# batsim1_2.net
KiCad netlist of a schematic drawn in EAGLE
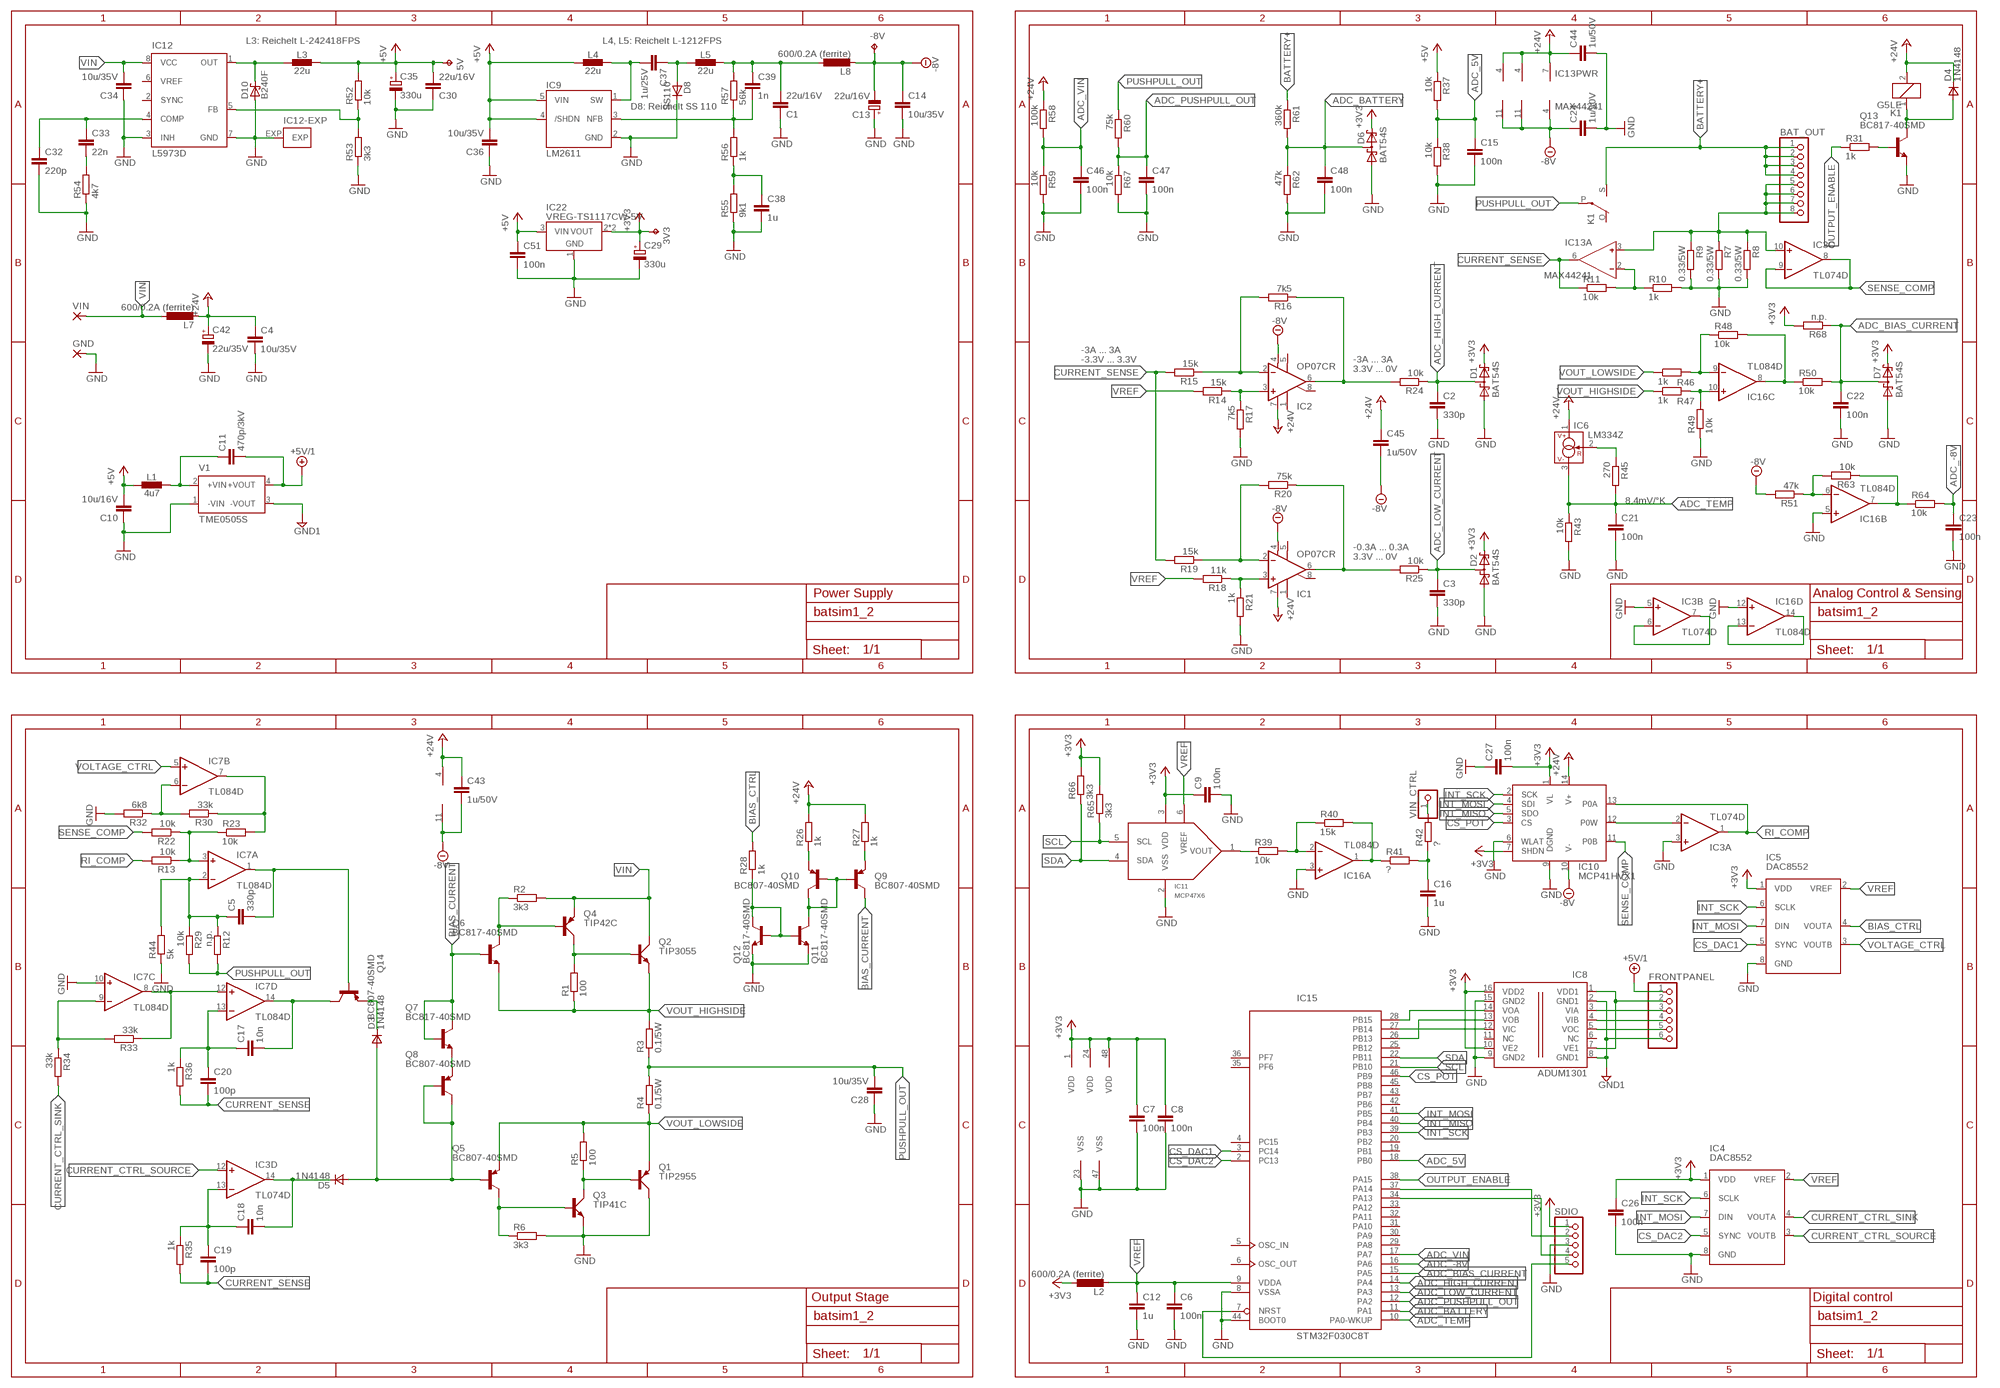
[diagram p0: schematic, sheet 1]

(export (version "E")
  (design (tool "Eeschema 10.0.6"))
  (components
    (comp (ref "-8V")
      (value "TPB1,27")
      (footprint "eagle-import:B1,27")
      (libsource (lib "eagle-import") (part "TPB1,27"))
    )
    (comp (ref "3V3")
      (value "TPB1,27")
      (footprint "eagle-import:B1,27")
      (libsource (lib "eagle-import") (part "TPB1,27"))
    )
    (comp (ref "5V")
      (value "TPB1,27")
      (footprint "eagle-import:B1,27")
      (libsource (lib "eagle-import") (part "TPB1,27"))
    )
    (comp (ref "BAT_OUT")
      (value "PINHD-1X8/90")
      (footprint "eagle-import:1X08_90")
      (libsource (lib "eagle-import") (part "PINHD-1X8/90"))
    )
    (comp (ref "C1")
      (value "22u/16V")
      (footprint "eagle-import:C1206")
      (libsource (lib "eagle-import") (part "C-EUC1206"))
    )
    (comp (ref "C2")
      (value "330p")
      (footprint "eagle-import:C0603")
      (libsource (lib "eagle-import") (part "C-EUC0603"))
    )
    (comp (ref "C3")
      (value "330p")
      (footprint "eagle-import:C0603")
      (libsource (lib "eagle-import") (part "C-EUC0603"))
    )
    (comp (ref "C4")
      (value "10u/35V")
      (footprint "eagle-import:C1206")
      (libsource (lib "eagle-import") (part "C-EUC1206"))
    )
    (comp (ref "C5")
      (value "330p")
      (footprint "eagle-import:C0603")
      (libsource (lib "eagle-import") (part "C-EUC0603"))
    )
    (comp (ref "C6")
      (value "100n")
      (footprint "eagle-import:C0603")
      (libsource (lib "eagle-import") (part "C-EUC0603"))
    )
    (comp (ref "C7")
      (value "100n")
      (footprint "eagle-import:C0603")
      (libsource (lib "eagle-import") (part "C-EUC0603"))
    )
    (comp (ref "C8")
      (value "100n")
      (footprint "eagle-import:C0603")
      (libsource (lib "eagle-import") (part "C-EUC0603"))
    )
    (comp (ref "C9")
      (value "100n")
      (footprint "eagle-import:C0603")
      (libsource (lib "eagle-import") (part "C-EUC0603"))
    )
    (comp (ref "C10")
      (value "10u/16V")
      (footprint "eagle-import:C1206")
      (libsource (lib "eagle-import") (part "C-EUC1206"))
    )
    (comp (ref "C11")
      (value "470p/3kV")
      (footprint "eagle-import:C1812")
      (libsource (lib "eagle-import") (part "resistor_C-EUC1812"))
    )
    (comp (ref "C12")
      (value "1u")
      (footprint "eagle-import:C0603")
      (libsource (lib "eagle-import") (part "C-EUC0603"))
    )
    (comp (ref "C13")
      (value "22u/16V")
      (footprint "eagle-import:153CLV-0505")
      (libsource (lib "eagle-import") (part "CPOL-EU153CLV-0505"))
    )
    (comp (ref "C14")
      (value "10u/35V")
      (footprint "eagle-import:C1206")
      (libsource (lib "eagle-import") (part "C-EUC1206"))
    )
    (comp (ref "C15")
      (value "100n")
      (footprint "eagle-import:C0603")
      (libsource (lib "eagle-import") (part "C-EUC0603"))
    )
    (comp (ref "C16")
      (value "1u")
      (footprint "eagle-import:C0603")
      (libsource (lib "eagle-import") (part "C-EUC0603"))
    )
    (comp (ref "C17")
      (value "10n")
      (footprint "eagle-import:C0603")
      (libsource (lib "eagle-import") (part "C-EUC0603"))
    )
    (comp (ref "C18")
      (value "10n")
      (footprint "eagle-import:C0603")
      (libsource (lib "eagle-import") (part "C-EUC0603"))
    )
    (comp (ref "C19")
      (value "100p")
      (footprint "eagle-import:C0603")
      (libsource (lib "eagle-import") (part "C-EUC0603"))
    )
    (comp (ref "C20")
      (value "100p")
      (footprint "eagle-import:C0603")
      (libsource (lib "eagle-import") (part "C-EUC0603"))
    )
    (comp (ref "C21")
      (value "100n")
      (footprint "eagle-import:C0603")
      (libsource (lib "eagle-import") (part "C-EUC0603"))
    )
    (comp (ref "C22")
      (value "100n")
      (footprint "eagle-import:C0603")
      (libsource (lib "eagle-import") (part "C-EUC0603"))
    )
    (comp (ref "C23")
      (value "100n")
      (footprint "eagle-import:C0603")
      (libsource (lib "eagle-import") (part "C-EUC0603"))
    )
    (comp (ref "C24")
      (value "1u/50V")
      (footprint "eagle-import:C0603")
      (libsource (lib "eagle-import") (part "C-EUC0603"))
    )
    (comp (ref "C26")
      (value "100n")
      (footprint "eagle-import:C0603")
      (libsource (lib "eagle-import") (part "C-EUC0603"))
    )
    (comp (ref "C27")
      (value "100n")
      (footprint "eagle-import:C0603")
      (libsource (lib "eagle-import") (part "C-EUC0603"))
    )
    (comp (ref "C28")
      (value "10u/35V")
      (footprint "eagle-import:C1206")
      (libsource (lib "eagle-import") (part "C-EUC1206"))
    )
    (comp (ref "C29")
      (value "330u")
      (footprint "eagle-import:153CLV-0605")
      (libsource (lib "eagle-import") (part "CPOL-EU153CLV-0605"))
    )
    (comp (ref "C30")
      (value "22u/16V")
      (footprint "eagle-import:C1206")
      (libsource (lib "eagle-import") (part "C-EUC1206"))
    )
    (comp (ref "C32")
      (value "220p")
      (footprint "eagle-import:C0603")
      (libsource (lib "eagle-import") (part "C-EUC0603"))
    )
    (comp (ref "C33")
      (value "22n")
      (footprint "eagle-import:C0603")
      (libsource (lib "eagle-import") (part "C-EUC0603"))
    )
    (comp (ref "C34")
      (value "10u/35V")
      (footprint "eagle-import:C1206")
      (libsource (lib "eagle-import") (part "C-EUC1206"))
    )
    (comp (ref "C35")
      (value "330u")
      (footprint "eagle-import:153CLV-0605")
      (libsource (lib "eagle-import") (part "CPOL-EU153CLV-0605"))
    )
    (comp (ref "C36")
      (value "10u/35V")
      (footprint "eagle-import:C1206")
      (libsource (lib "eagle-import") (part "C-EUC1206"))
    )
    (comp (ref "C37")
      (value "1u/25V")
      (footprint "eagle-import:C1206")
      (libsource (lib "eagle-import") (part "C-EUC1206"))
    )
    (comp (ref "C38")
      (value "1u")
      (footprint "eagle-import:C0603")
      (libsource (lib "eagle-import") (part "C-EUC0603"))
    )
    (comp (ref "C39")
      (value "1n")
      (footprint "eagle-import:C0603")
      (libsource (lib "eagle-import") (part "C-EUC0603"))
    )
    (comp (ref "C42")
      (value "22u/35V")
      (footprint "eagle-import:153CLV-0605")
      (libsource (lib "eagle-import") (part "CPOL-EU153CLV-0605"))
    )
    (comp (ref "C43")
      (value "1u/50V")
      (footprint "eagle-import:C0603")
      (libsource (lib "eagle-import") (part "C-EUC0603"))
    )
    (comp (ref "C44")
      (value "1u/50V")
      (footprint "eagle-import:C0603")
      (libsource (lib "eagle-import") (part "C-EUC0603"))
    )
    (comp (ref "C45")
      (value "1u/50V")
      (footprint "eagle-import:C0603")
      (libsource (lib "eagle-import") (part "C-EUC0603"))
    )
    (comp (ref "C46")
      (value "100n")
      (footprint "eagle-import:C0603")
      (libsource (lib "eagle-import") (part "C-EUC0603"))
    )
    (comp (ref "C47")
      (value "100n")
      (footprint "eagle-import:C0603")
      (libsource (lib "eagle-import") (part "C-EUC0603"))
    )
    (comp (ref "C48")
      (value "100n")
      (footprint "eagle-import:C0603")
      (libsource (lib "eagle-import") (part "C-EUC0603"))
    )
    (comp (ref "C51")
      (value "100n")
      (footprint "eagle-import:C0603")
      (libsource (lib "eagle-import") (part "C-EUC0603"))
    )
    (comp (ref "D1")
      (value "BAT54S")
      (footprint "eagle-import:SOT23")
      (libsource (lib "eagle-import") (part "BAT54S"))
    )
    (comp (ref "D2")
      (value "BAT54S")
      (footprint "eagle-import:SOT23")
      (libsource (lib "eagle-import") (part "BAT54S"))
    )
    (comp (ref "D3")
      (value "1N4148")
      (footprint "eagle-import:SOD323")
      (fields (field (name "MPN") "CDSOD323-T05C"))
      (libsource (lib "eagle-import") (part "DSOD323"))
    )
    (comp (ref "D4")
      (value "1N4148")
      (footprint "eagle-import:SOD323")
      (fields (field (name "MPN") "CDSOD323-T05C"))
      (libsource (lib "eagle-import") (part "DSOD323"))
    )
    (comp (ref "D5")
      (value "1N4148")
      (footprint "eagle-import:SOD323")
      (fields (field (name "MPN") "CDSOD323-T05C"))
      (libsource (lib "eagle-import") (part "DSOD323"))
    )
    (comp (ref "D6")
      (value "BAT54S")
      (footprint "eagle-import:SOT23")
      (libsource (lib "eagle-import") (part "BAT54S"))
    )
    (comp (ref "D7")
      (value "BAT54S")
      (footprint "eagle-import:SOT23")
      (libsource (lib "eagle-import") (part "BAT54S"))
    )
    (comp (ref "D8")
      (value "SS110")
      (footprint "eagle-import:SMA")
      (libsource (lib "eagle-import") (part "D-SMA"))
    )
    (comp (ref "D10")
      (value "B240F")
      (footprint "eagle-import:SMB")
      (libsource (lib "eagle-import") (part "SCHOTTKY-DIODESMD"))
    )
    (comp (ref "FRONTPANEL")
      (value "PINHD-1X6/90")
      (footprint "eagle-import:1X06_90")
      (libsource (lib "eagle-import") (part "PINHD-1X6/90"))
    )
    (comp (ref "GND")
      (value "3,81/1,4")
      (footprint "eagle-import:3,81_1,4")
      (libsource (lib "eagle-import") (part "3,81/1,4"))
    )
    (comp (ref "IC1")
      (value "OP07CR")
      (footprint "eagle-import:SO08")
      (libsource (lib "eagle-import") (part "OP07RC"))
    )
    (comp (ref "IC2")
      (value "OP07CR")
      (footprint "eagle-import:SO08")
      (libsource (lib "eagle-import") (part "OP07RC"))
    )
    (comp (ref "IC3")
      (value "TL074D")
      (footprint "eagle-import:SO14")
      (libsource (lib "eagle-import") (part "TL074D"))
    )
    (comp (ref "IC4")
      (value "DAC8552")
      (footprint "eagle-import:MSOP8")
      (libsource (lib "eagle-import") (part "DAC8552"))
    )
    (comp (ref "IC5")
      (value "DAC8552")
      (footprint "eagle-import:MSOP8")
      (libsource (lib "eagle-import") (part "DAC8552"))
    )
    (comp (ref "IC6")
      (value "LM334Z")
      (footprint "eagle-import:TO92")
      (libsource (lib "eagle-import") (part "LM34Z3"))
    )
    (comp (ref "IC7")
      (value "TL084D")
      (footprint "eagle-import:SO14")
      (libsource (lib "eagle-import") (part "TL084D"))
    )
    (comp (ref "IC8")
      (value "ADUM1301")
      (footprint "eagle-import:SO-16W")
      (fields (field (name "MPN") "ADUM1301BRWZ"))
      (libsource (lib "eagle-import") (part "ADUM1301"))
    )
    (comp (ref "IC9")
      (value "LM2611")
      (footprint "eagle-import:SOT23-5")
      (libsource (lib "eagle-import") (part "LM2611"))
    )
    (comp (ref "IC10")
      (value "MCP41HVX1")
      (footprint "eagle-import:TSSOP14")
      (libsource (lib "eagle-import") (part "MCP41HVX1"))
    )
    (comp (ref "IC11")
      (value "MCP47X6")
      (footprint "eagle-import:SOT23-6L")
      (libsource (lib "eagle-import") (part "MCP47X6"))
    )
    (comp (ref "IC12")
      (value "L5973D")
      (footprint "eagle-import:HSOP8")
      (fields (field (name "MF") "STMICROELECTRONICS"))
      (libsource (lib "eagle-import") (part "L5973D"))
    )
    (comp (ref "IC13")
      (value "MAX44241")
      (footprint "eagle-import:UMAX8")
      (libsource (lib "eagle-import") (part "MAX44241"))
    )
    (comp (ref "IC15")
      (value "STM32F030C8T")
      (footprint "eagle-import:LQFP48")
      (libsource (lib "eagle-import") (part "STM32F030CT8"))
    )
    (comp (ref "IC16")
      (value "TL084D")
      (footprint "eagle-import:SO14")
      (libsource (lib "eagle-import") (part "TL084D"))
    )
    (comp (ref "IC22")
      (value "VREG-TS1117CW-5V")
      (footprint "eagle-import:SOT223")
      (libsource (lib "eagle-import") (part "VREG-TS1117CW-5V"))
    )
    (comp (ref "K1")
      (value "G5LE")
      (footprint "eagle-import:G5LE")
      (libsource (lib "eagle-import") (part "G5LE"))
    )
    (comp (ref "L1")
      (value "4u7")
      (footprint "eagle-import:L_1212")
      (libsource (lib "eagle-import") (part "INDUCTOR-1212"))
    )
    (comp (ref "L2")
      (value "600/0.2A (ferrite)")
      (footprint "eagle-import:L2012C")
      (libsource (lib "eagle-import") (part "L-EUL2012C"))
    )
    (comp (ref "L3")
      (value "22u")
      (footprint "eagle-import:L_NR60XX")
      (libsource (lib "eagle-import") (part "INDUCTOR-NR60XX"))
    )
    (comp (ref "L4")
      (value "22u")
      (footprint "eagle-import:L_1212")
      (libsource (lib "eagle-import") (part "INDUCTOR-1212"))
    )
    (comp (ref "L5")
      (value "22u")
      (footprint "eagle-import:L_1212")
      (libsource (lib "eagle-import") (part "INDUCTOR-1212"))
    )
    (comp (ref "L7")
      (value "600/0.2A (ferrite)")
      (footprint "eagle-import:L2012C")
      (libsource (lib "eagle-import") (part "L-EUL2012C"))
    )
    (comp (ref "L8")
      (value "600/0.2A (ferrite)")
      (footprint "eagle-import:L2012C")
      (libsource (lib "eagle-import") (part "L-EUL2012C"))
    )
    (comp (ref "Q1")
      (value "TIP2955")
      (footprint "eagle-import:TOP3AV")
      (libsource (lib "eagle-import") (part "TIP2955"))
    )
    (comp (ref "Q2")
      (value "TIP3055")
      (footprint "eagle-import:TOP3AV")
      (libsource (lib "eagle-import") (part "TIP3055"))
    )
    (comp (ref "Q3")
      (value "TIP41C")
      (footprint "eagle-import:TO220AV")
      (libsource (lib "eagle-import") (part "TIP41C"))
    )
    (comp (ref "Q4")
      (value "TIP42C")
      (footprint "eagle-import:TO220AV")
      (libsource (lib "eagle-import") (part "TIP42C"))
    )
    (comp (ref "Q5")
      (value "BC807-40SMD")
      (footprint "eagle-import:SOT23-BEC")
      (libsource (lib "eagle-import") (part "BC807SMD-40"))
    )
    (comp (ref "Q6")
      (value "BC817-40SMD")
      (footprint "eagle-import:SOT23-BEC")
      (libsource (lib "eagle-import") (part "BC817SMD-40"))
    )
    (comp (ref "Q7")
      (value "BC817-40SMD")
      (footprint "eagle-import:SOT23-BEC")
      (libsource (lib "eagle-import") (part "BC817SMD-40"))
    )
    (comp (ref "Q8")
      (value "BC807-40SMD")
      (footprint "eagle-import:SOT23-BEC")
      (libsource (lib "eagle-import") (part "BC807SMD-40"))
    )
    (comp (ref "Q9")
      (value "BC807-40SMD")
      (footprint "eagle-import:SOT23-BEC")
      (libsource (lib "eagle-import") (part "BC807SMD-40"))
    )
    (comp (ref "Q10")
      (value "BC807-40SMD")
      (footprint "eagle-import:SOT23-BEC")
      (libsource (lib "eagle-import") (part "BC807SMD-40"))
    )
    (comp (ref "Q11")
      (value "BC817-40SMD")
      (footprint "eagle-import:SOT23-BEC")
      (libsource (lib "eagle-import") (part "BC817SMD-40"))
    )
    (comp (ref "Q12")
      (value "BC817-40SMD")
      (footprint "eagle-import:SOT23-BEC")
      (libsource (lib "eagle-import") (part "BC817SMD-40"))
    )
    (comp (ref "Q13")
      (value "BC817-40SMD")
      (footprint "eagle-import:SOT23-BEC")
      (libsource (lib "eagle-import") (part "BC817SMD-40"))
    )
    (comp (ref "Q14")
      (value "BC807-40SMD")
      (footprint "eagle-import:SOT23-BEC")
      (libsource (lib "eagle-import") (part "BC807SMD-40"))
    )
    (comp (ref "R1")
      (value "100")
      (footprint "eagle-import:R0603")
      (libsource (lib "eagle-import") (part "R-EU_R0603"))
    )
    (comp (ref "R2")
      (value "3k3")
      (footprint "eagle-import:R0603")
      (libsource (lib "eagle-import") (part "R-EU_R0603"))
    )
    (comp (ref "R3")
      (value "0.1/5W")
      (footprint "eagle-import:5WAXIAL")
      (libsource (lib "eagle-import") (part "5WAXIAL"))
    )
    (comp (ref "R4")
      (value "0.1/5W")
      (footprint "eagle-import:5WAXIAL")
      (libsource (lib "eagle-import") (part "5WAXIAL"))
    )
    (comp (ref "R5")
      (value "100")
      (footprint "eagle-import:R0603")
      (libsource (lib "eagle-import") (part "R-EU_R0603"))
    )
    (comp (ref "R6")
      (value "3k3")
      (footprint "eagle-import:R0603")
      (libsource (lib "eagle-import") (part "R-EU_R0603"))
    )
    (comp (ref "R7")
      (value "0.33/5W")
      (footprint "eagle-import:5WAXIAL")
      (libsource (lib "eagle-import") (part "5WAXIAL"))
    )
    (comp (ref "R8")
      (value "0.33/5W")
      (footprint "eagle-import:5WAXIAL")
      (libsource (lib "eagle-import") (part "5WAXIAL"))
    )
    (comp (ref "R9")
      (value "0.33/5W")
      (footprint "eagle-import:5WAXIAL")
      (libsource (lib "eagle-import") (part "5WAXIAL"))
    )
    (comp (ref "R10")
      (value "1k")
      (footprint "eagle-import:R0603")
      (libsource (lib "eagle-import") (part "R-EU_R0603"))
    )
    (comp (ref "R11")
      (value "10k")
      (footprint "eagle-import:R0603")
      (libsource (lib "eagle-import") (part "R-EU_R0603"))
    )
    (comp (ref "R12")
      (value "n.p.")
      (footprint "eagle-import:R0603")
      (libsource (lib "eagle-import") (part "R-EU_R0603"))
    )
    (comp (ref "R13")
      (value "10k")
      (footprint "eagle-import:R0603")
      (libsource (lib "eagle-import") (part "R-EU_R0603"))
    )
    (comp (ref "R14")
      (value "15k")
      (footprint "eagle-import:R0603")
      (libsource (lib "eagle-import") (part "R-EU_R0603"))
    )
    (comp (ref "R15")
      (value "15k")
      (footprint "eagle-import:R0603")
      (libsource (lib "eagle-import") (part "R-EU_R0603"))
    )
    (comp (ref "R16")
      (value "7k5")
      (footprint "eagle-import:R0603")
      (libsource (lib "eagle-import") (part "R-EU_R0603"))
    )
    (comp (ref "R17")
      (value "7k5")
      (footprint "eagle-import:R0603")
      (libsource (lib "eagle-import") (part "R-EU_R0603"))
    )
    (comp (ref "R18")
      (value "11k")
      (footprint "eagle-import:R0603")
      (libsource (lib "eagle-import") (part "R-EU_R0603"))
    )
    (comp (ref "R19")
      (value "15k")
      (footprint "eagle-import:R0603")
      (libsource (lib "eagle-import") (part "R-EU_R0603"))
    )
    (comp (ref "R20")
      (value "75k")
      (footprint "eagle-import:R0603")
      (libsource (lib "eagle-import") (part "R-EU_R0603"))
    )
    (comp (ref "R21")
      (value "1k")
      (footprint "eagle-import:R0603")
      (libsource (lib "eagle-import") (part "R-EU_R0603"))
    )
    (comp (ref "R22")
      (value "10k")
      (footprint "eagle-import:R0603")
      (libsource (lib "eagle-import") (part "R-EU_R0603"))
    )
    (comp (ref "R23")
      (value "10k")
      (footprint "eagle-import:R0603")
      (libsource (lib "eagle-import") (part "R-EU_R0603"))
    )
    (comp (ref "R24")
      (value "10k")
      (footprint "eagle-import:R0603")
      (libsource (lib "eagle-import") (part "R-EU_R0603"))
    )
    (comp (ref "R25")
      (value "10k")
      (footprint "eagle-import:R0603")
      (libsource (lib "eagle-import") (part "R-EU_R0603"))
    )
    (comp (ref "R26")
      (value "1k")
      (footprint "eagle-import:R0603")
      (libsource (lib "eagle-import") (part "R-EU_R0603"))
    )
    (comp (ref "R27")
      (value "1k")
      (footprint "eagle-import:R0603")
      (libsource (lib "eagle-import") (part "R-EU_R0603"))
    )
    (comp (ref "R28")
      (value "1k")
      (footprint "eagle-import:R0603")
      (libsource (lib "eagle-import") (part "R-EU_R0603"))
    )
    (comp (ref "R29")
      (value "10k")
      (footprint "eagle-import:R0603")
      (libsource (lib "eagle-import") (part "R-EU_R0603"))
    )
    (comp (ref "R30")
      (value "33k")
      (footprint "eagle-import:R0603")
      (libsource (lib "eagle-import") (part "R-EU_R0603"))
    )
    (comp (ref "R31")
      (value "1k")
      (footprint "eagle-import:R0603")
      (libsource (lib "eagle-import") (part "R-EU_R0603"))
    )
    (comp (ref "R32")
      (value "6k8")
      (footprint "eagle-import:R0603")
      (libsource (lib "eagle-import") (part "R-EU_R0603"))
    )
    (comp (ref "R33")
      (value "33k")
      (footprint "eagle-import:R0603")
      (libsource (lib "eagle-import") (part "R-EU_R0603"))
    )
    (comp (ref "R34")
      (value "33k")
      (footprint "eagle-import:R0603")
      (libsource (lib "eagle-import") (part "R-EU_R0603"))
    )
    (comp (ref "R35")
      (value "1k")
      (footprint "eagle-import:R0603")
      (libsource (lib "eagle-import") (part "R-EU_R0603"))
    )
    (comp (ref "R36")
      (value "1k")
      (footprint "eagle-import:R0603")
      (libsource (lib "eagle-import") (part "R-EU_R0603"))
    )
    (comp (ref "R37")
      (value "10k")
      (footprint "eagle-import:R0603")
      (libsource (lib "eagle-import") (part "R-EU_R0603"))
    )
    (comp (ref "R38")
      (value "10k")
      (footprint "eagle-import:R0603")
      (libsource (lib "eagle-import") (part "R-EU_R0603"))
    )
    (comp (ref "R39")
      (value "10k")
      (footprint "eagle-import:R0603")
      (libsource (lib "eagle-import") (part "R-EU_R0603"))
    )
    (comp (ref "R40")
      (value "15k")
      (footprint "eagle-import:R0603")
      (libsource (lib "eagle-import") (part "R-EU_R0603"))
    )
    (comp (ref "R41")
      (value "?")
      (footprint "eagle-import:R0603")
      (libsource (lib "eagle-import") (part "R-EU_R0603"))
    )
    (comp (ref "R42")
      (value "?")
      (footprint "eagle-import:R0603")
      (libsource (lib "eagle-import") (part "R-EU_R0603"))
    )
    (comp (ref "R43")
      (value "10k")
      (footprint "eagle-import:R0603")
      (libsource (lib "eagle-import") (part "R-EU_R0603"))
    )
    (comp (ref "R44")
      (value "5k")
      (footprint "eagle-import:R0603")
      (libsource (lib "eagle-import") (part "R-EU_R0603"))
    )
    (comp (ref "R45")
      (value "270")
      (footprint "eagle-import:R0603")
      (libsource (lib "eagle-import") (part "R-EU_R0603"))
    )
    (comp (ref "R46")
      (value "1k")
      (footprint "eagle-import:R0603")
      (libsource (lib "eagle-import") (part "R-EU_R0603"))
    )
    (comp (ref "R47")
      (value "1k")
      (footprint "eagle-import:R0603")
      (libsource (lib "eagle-import") (part "R-EU_R0603"))
    )
    (comp (ref "R48")
      (value "10k")
      (footprint "eagle-import:R0603")
      (libsource (lib "eagle-import") (part "R-EU_R0603"))
    )
    (comp (ref "R49")
      (value "10k")
      (footprint "eagle-import:R0603")
      (libsource (lib "eagle-import") (part "R-EU_R0603"))
    )
    (comp (ref "R50")
      (value "10k")
      (footprint "eagle-import:R0603")
      (libsource (lib "eagle-import") (part "R-EU_R0603"))
    )
    (comp (ref "R51")
      (value "47k")
      (footprint "eagle-import:R0603")
      (libsource (lib "eagle-import") (part "R-EU_R0603"))
    )
    (comp (ref "R52")
      (value "10k")
      (footprint "eagle-import:R0603")
      (libsource (lib "eagle-import") (part "R-EU_R0603"))
    )
    (comp (ref "R53")
      (value "3k3")
      (footprint "eagle-import:R0603")
      (libsource (lib "eagle-import") (part "R-EU_R0603"))
    )
    (comp (ref "R54")
      (value "4k7")
      (footprint "eagle-import:R0603")
      (libsource (lib "eagle-import") (part "R-EU_R0603"))
    )
    (comp (ref "R55")
      (value "9k1")
      (footprint "eagle-import:R0603")
      (libsource (lib "eagle-import") (part "R-EU_R0603"))
    )
    (comp (ref "R56")
      (value "1k")
      (footprint "eagle-import:R0603")
      (libsource (lib "eagle-import") (part "R-EU_R0603"))
    )
    (comp (ref "R57")
      (value "56k")
      (footprint "eagle-import:R0603")
      (libsource (lib "eagle-import") (part "R-EU_R0603"))
    )
    (comp (ref "R58")
      (value "100k")
      (footprint "eagle-import:R0603")
      (libsource (lib "eagle-import") (part "R-EU_R0603"))
    )
    (comp (ref "R59")
      (value "10k")
      (footprint "eagle-import:R0603")
      (libsource (lib "eagle-import") (part "R-EU_R0603"))
    )
    (comp (ref "R60")
      (value "75k")
      (footprint "eagle-import:R0603")
      (libsource (lib "eagle-import") (part "R-EU_R0603"))
    )
    (comp (ref "R61")
      (value "360k")
      (footprint "eagle-import:R0603")
      (libsource (lib "eagle-import") (part "R-EU_R0603"))
    )
    (comp (ref "R62")
      (value "47k")
      (footprint "eagle-import:R0603")
      (libsource (lib "eagle-import") (part "R-EU_R0603"))
    )
    (comp (ref "R63")
      (value "10k")
      (footprint "eagle-import:R0603")
      (libsource (lib "eagle-import") (part "R-EU_R0603"))
    )
    (comp (ref "R64")
      (value "10k")
      (footprint "eagle-import:R0603")
      (libsource (lib "eagle-import") (part "R-EU_R0603"))
    )
    (comp (ref "R65")
      (value "3k3")
      (footprint "eagle-import:R0603")
      (libsource (lib "eagle-import") (part "R-EU_R0603"))
    )
    (comp (ref "R66")
      (value "3k3")
      (footprint "eagle-import:R0603")
      (libsource (lib "eagle-import") (part "R-EU_R0603"))
    )
    (comp (ref "R67")
      (value "10k")
      (footprint "eagle-import:R0603")
      (libsource (lib "eagle-import") (part "R-EU_R0603"))
    )
    (comp (ref "R68")
      (value "n.p.")
      (footprint "eagle-import:R0603")
      (libsource (lib "eagle-import") (part "R-EU_R0603"))
    )
    (comp (ref "SDIO")
      (value "PINHD-1X5")
      (footprint "eagle-import:1X05")
      (libsource (lib "eagle-import") (part "PINHD-1X5"))
    )
    (comp (ref "V1")
      (value "TME0505S")
      (footprint "eagle-import:TME")
      (fields (field (name "MPN") "TME 0505S"))
      (libsource (lib "eagle-import") (part "TME?0505S"))
    )
    (comp (ref "VIN")
      (value "3,81/1,4")
      (footprint "eagle-import:3,81_1,4")
      (libsource (lib "eagle-import") (part "3,81/1,4"))
    )
    (comp (ref "VIN_CTRL")
      (value "PINHD-1X1")
      (footprint "eagle-import:1X01")
      (libsource (lib "eagle-import") (part "PINHD-1X1"))
    )
  )
  (nets
    (net (code "1") (name "+3V3") (class "Default")
      (node (ref "3V3") (pin "TP") (pinfunction "TP_TP") (pintype "input"))
      (node (ref "C26") (pin "1") (pinfunction "1_1") (pintype "passive"))
      (node (ref "C27") (pin "2") (pinfunction "2_2") (pintype "passive"))
      (node (ref "C29") (pin "+") (pinfunction "+_+") (pintype "passive"))
      (node (ref "C7") (pin "1") (pinfunction "1_1") (pintype "passive"))
      (node (ref "C8") (pin "1") (pinfunction "1_1") (pintype "passive"))
      (node (ref "C9") (pin "1") (pinfunction "1_1") (pintype "passive"))
      (node (ref "D1") (pin "2") (pinfunction "C2_2") (pintype "passive"))
      (node (ref "D2") (pin "2") (pinfunction "C2_2") (pintype "passive"))
      (node (ref "D6") (pin "2") (pinfunction "C2_2") (pintype "passive"))
      (node (ref "D7") (pin "2") (pinfunction "C2_2") (pintype "passive"))
      (node (ref "IC10") (pin "1") (pinfunction "VL_1") (pintype "bidirectional"))
      (node (ref "IC10") (pin "7") (pinfunction "SHDN_7") (pintype "bidirectional"))
      (node (ref "IC11") (pin "3") (pinfunction "VDD_3") (pintype "bidirectional"))
      (node (ref "IC15") (pin "1") (pinfunction "VDD_1") (pintype "power_in"))
      (node (ref "IC15") (pin "24") (pinfunction "VDD_24") (pintype "power_in"))
      (node (ref "IC15") (pin "48") (pinfunction "VDD_48") (pintype "power_in"))
      (node (ref "IC22") (pin "2") (pinfunction "VOUT_2") (pintype "power_in"))
      (node (ref "IC22") (pin "4") (pinfunction "VOUT_4") (pintype "power_in"))
      (node (ref "IC4") (pin "1") (pinfunction "VDD_1") (pintype "power_in"))
      (node (ref "IC5") (pin "1") (pinfunction "VDD_1") (pintype "power_in"))
      (node (ref "IC8") (pin "10") (pinfunction "VE2_10") (pintype "input"))
      (node (ref "IC8") (pin "16") (pinfunction "VDD2_16") (pintype "input"))
      (node (ref "L2") (pin "1") (pinfunction "1_1") (pintype "passive"))
      (node (ref "R65") (pin "2") (pinfunction "2_2") (pintype "passive"))
      (node (ref "R66") (pin "2") (pinfunction "2_2") (pintype "passive"))
      (node (ref "R68") (pin "2") (pinfunction "2_2") (pintype "passive"))
      (node (ref "SDIO") (pin "1") (pinfunction "1_1") (pintype "passive"))
    )
    (net (code "2") (name "+5V") (class "Default")
      (node (ref "5V") (pin "TP") (pinfunction "TP_TP") (pintype "input"))
      (node (ref "C10") (pin "2") (pinfunction "2_2") (pintype "passive"))
      (node (ref "C30") (pin "2") (pinfunction "2_2") (pintype "passive"))
      (node (ref "C35") (pin "+") (pinfunction "+_+") (pintype "passive"))
      (node (ref "C36") (pin "2") (pinfunction "2_2") (pintype "passive"))
      (node (ref "C51") (pin "1") (pinfunction "1_1") (pintype "passive"))
      (node (ref "IC22") (pin "3") (pinfunction "VIN_3") (pintype "power_in"))
      (node (ref "IC9") (pin "4") (pinfunction "/SHDN_4") (pintype "input"))
      (node (ref "IC9") (pin "5") (pinfunction "VIN_5") (pintype "power_in"))
      (node (ref "L1") (pin "1") (pinfunction "1_1") (pintype "passive"))
      (node (ref "L3") (pin "2") (pinfunction "2_2") (pintype "passive"))
      (node (ref "L4") (pin "1") (pinfunction "1_1") (pintype "passive"))
      (node (ref "R37") (pin "1") (pinfunction "1_1") (pintype "passive"))
      (node (ref "R52") (pin "2") (pinfunction "2_2") (pintype "passive"))
    )
    (net (code "3") (name "+5V{slash}1") (class "Default")
      (node (ref "C11") (pin "2") (pinfunction "2_2") (pintype "passive"))
      (node (ref "FRONTPANEL") (pin "1") (pinfunction "1_1") (pintype "passive"))
      (node (ref "V1") (pin "4") (pinfunction "+VOUT_4") (pintype "passive"))
    )
    (net (code "4") (name "+24V") (class "Default")
      (node (ref "C4") (pin "1") (pinfunction "1_1") (pintype "passive"))
      (node (ref "C42") (pin "+") (pinfunction "+_+") (pintype "passive"))
      (node (ref "C43") (pin "1") (pinfunction "1_1") (pintype "passive"))
      (node (ref "C44") (pin "1") (pinfunction "1_1") (pintype "passive"))
      (node (ref "C45") (pin "1") (pinfunction "1_1") (pintype "passive"))
      (node (ref "D4") (pin "1") (pinfunction "C_1") (pintype "passive"))
      (node (ref "IC1") (pin "7") (pinfunction "V+_7") (pintype "power_in"))
      (node (ref "IC10") (pin "14") (pinfunction "V+_14") (pintype "bidirectional"))
      (node (ref "IC13") (pin "7") (pinfunction "V+_7") (pintype "power_in"))
      (node (ref "IC16") (pin "4") (pinfunction "V+_4") (pintype "power_in"))
      (node (ref "IC2") (pin "7") (pinfunction "V+_7") (pintype "power_in"))
      (node (ref "IC3") (pin "4") (pinfunction "V+_4") (pintype "power_in"))
      (node (ref "IC6") (pin "1") (pinfunction "V+_1") (pintype "passive"))
      (node (ref "IC7") (pin "4") (pinfunction "V+_4") (pintype "power_in"))
      (node (ref "K1") (pin "2") (pinfunction "2_2") (pintype "passive"))
      (node (ref "L7") (pin "2") (pinfunction "2_2") (pintype "passive"))
      (node (ref "R26") (pin "2") (pinfunction "2_2") (pintype "passive"))
      (node (ref "R27") (pin "2") (pinfunction "2_2") (pintype "passive"))
      (node (ref "R58") (pin "1") (pinfunction "1_1") (pintype "passive"))
    )
    (net (code "5") (name "-8V") (class "Default")
      (node (ref "-8V") (pin "TP") (pinfunction "TP_TP") (pintype "input"))
      (node (ref "C13") (pin "-") (pinfunction "-_-") (pintype "passive"))
      (node (ref "C14") (pin "1") (pinfunction "1_1") (pintype "passive"))
      (node (ref "C24") (pin "1") (pinfunction "1_1") (pintype "passive"))
      (node (ref "C43") (pin "2") (pinfunction "2_2") (pintype "passive"))
      (node (ref "C45") (pin "2") (pinfunction "2_2") (pintype "passive"))
      (node (ref "IC1") (pin "4") (pinfunction "V-_4") (pintype "power_in"))
      (node (ref "IC10") (pin "10") (pinfunction "V-_10") (pintype "bidirectional"))
      (node (ref "IC13") (pin "4") (pinfunction "V-_4") (pintype "power_in"))
      (node (ref "IC16") (pin "11") (pinfunction "V-_11") (pintype "power_in"))
      (node (ref "IC2") (pin "4") (pinfunction "V-_4") (pintype "power_in"))
      (node (ref "IC3") (pin "11") (pinfunction "V-_11") (pintype "power_in"))
      (node (ref "IC7") (pin "11") (pinfunction "V-_11") (pintype "power_in"))
      (node (ref "L8") (pin "2") (pinfunction "2_2") (pintype "passive"))
      (node (ref "R51") (pin "2") (pinfunction "2_2") (pintype "passive"))
    )
    (net (code "6") (name "ADC_-8V") (class "Default")
      (node (ref "C23") (pin "1") (pinfunction "1_1") (pintype "passive"))
      (node (ref "IC15") (pin "16") (pinfunction "PA6_16") (pintype "bidirectional"))
      (node (ref "R64") (pin "2") (pinfunction "2_2") (pintype "passive"))
    )
    (net (code "7") (name "ADC_5V") (class "Default")
      (node (ref "C15") (pin "1") (pinfunction "1_1") (pintype "passive"))
      (node (ref "IC15") (pin "18") (pinfunction "PB0_18") (pintype "bidirectional"))
      (node (ref "R37") (pin "2") (pinfunction "2_2") (pintype "passive"))
      (node (ref "R38") (pin "1") (pinfunction "1_1") (pintype "passive"))
    )
    (net (code "8") (name "ADC_BATTERY") (class "Default")
      (node (ref "C48") (pin "1") (pinfunction "1_1") (pintype "passive"))
      (node (ref "D6") (pin "3") (pinfunction "C1A2_3") (pintype "passive"))
      (node (ref "IC15") (pin "11") (pinfunction "PA1_11") (pintype "bidirectional"))
      (node (ref "R61") (pin "2") (pinfunction "2_2") (pintype "passive"))
      (node (ref "R62") (pin "1") (pinfunction "1_1") (pintype "passive"))
    )
    (net (code "9") (name "ADC_BIAS_CURRENT") (class "Default")
      (node (ref "C22") (pin "1") (pinfunction "1_1") (pintype "passive"))
      (node (ref "D7") (pin "3") (pinfunction "C1A2_3") (pintype "passive"))
      (node (ref "IC15") (pin "15") (pinfunction "PA5_15") (pintype "bidirectional"))
      (node (ref "R50") (pin "2") (pinfunction "2_2") (pintype "passive"))
      (node (ref "R68") (pin "1") (pinfunction "1_1") (pintype "passive"))
    )
    (net (code "10") (name "ADC_HIGH_CURRENT") (class "Default")
      (node (ref "C2") (pin "1") (pinfunction "1_1") (pintype "passive"))
      (node (ref "D1") (pin "3") (pinfunction "C1A2_3") (pintype "passive"))
      (node (ref "IC15") (pin "14") (pinfunction "PA4_14") (pintype "bidirectional"))
      (node (ref "R24") (pin "1") (pinfunction "1_1") (pintype "passive"))
    )
    (net (code "11") (name "ADC_LOW_CURRENT") (class "Default")
      (node (ref "C3") (pin "1") (pinfunction "1_1") (pintype "passive"))
      (node (ref "D2") (pin "3") (pinfunction "C1A2_3") (pintype "passive"))
      (node (ref "IC15") (pin "13") (pinfunction "PA3_13") (pintype "bidirectional"))
      (node (ref "R25") (pin "1") (pinfunction "1_1") (pintype "passive"))
    )
    (net (code "12") (name "ADC_PUSHPULL_OUT") (class "Default")
      (node (ref "C47") (pin "1") (pinfunction "1_1") (pintype "passive"))
      (node (ref "IC15") (pin "12") (pinfunction "PA2_12") (pintype "bidirectional"))
      (node (ref "R60") (pin "2") (pinfunction "2_2") (pintype "passive"))
      (node (ref "R67") (pin "1") (pinfunction "1_1") (pintype "passive"))
    )
    (net (code "13") (name "ADC_TEMP") (class "Default")
      (node (ref "C21") (pin "1") (pinfunction "1_1") (pintype "passive"))
      (node (ref "IC15") (pin "10") (pinfunction "PA0-WKUP_10") (pintype "bidirectional"))
      (node (ref "IC6") (pin "3") (pinfunction "V-_3") (pintype "passive"))
      (node (ref "R43") (pin "1") (pinfunction "1_1") (pintype "passive"))
      (node (ref "R45") (pin "2") (pinfunction "2_2") (pintype "passive"))
    )
    (net (code "14") (name "ADC_VIN") (class "Default")
      (node (ref "C46") (pin "1") (pinfunction "1_1") (pintype "passive"))
      (node (ref "IC15") (pin "17") (pinfunction "PA7_17") (pintype "bidirectional"))
      (node (ref "R58") (pin "2") (pinfunction "2_2") (pintype "passive"))
      (node (ref "R59") (pin "1") (pinfunction "1_1") (pintype "passive"))
    )
    (net (code "15") (name "BATTERY+") (class "Default")
      (node (ref "BAT_OUT") (pin "1") (pinfunction "1_1") (pintype "passive"))
      (node (ref "BAT_OUT") (pin "2") (pinfunction "2_2") (pintype "passive"))
      (node (ref "BAT_OUT") (pin "3") (pinfunction "3_3") (pintype "passive"))
      (node (ref "BAT_OUT") (pin "4") (pinfunction "4_4") (pintype "passive"))
      (node (ref "K1") (pin "S") (pinfunction "S_S") (pintype "passive"))
      (node (ref "R61") (pin "1") (pinfunction "1_1") (pintype "passive"))
    )
    (net (code "16") (name "BIAS_CTRL") (class "Default")
      (node (ref "IC5") (pin "4") (pinfunction "VOUTA_4") (pintype "output"))
      (node (ref "R28") (pin "2") (pinfunction "2_2") (pintype "passive"))
    )
    (net (code "17") (name "BIAS_CURRENT") (class "Default")
      (node (ref "Q6") (pin "B") (pinfunction "B_B") (pintype "passive"))
      (node (ref "Q7") (pin "B") (pinfunction "B_B") (pintype "passive"))
      (node (ref "Q7") (pin "C") (pinfunction "C_C") (pintype "passive"))
      (node (ref "Q9") (pin "C") (pinfunction "C_C") (pintype "passive"))
    )
    (net (code "18") (name "CS_DAC1") (class "Default")
      (node (ref "IC15") (pin "3") (pinfunction "PC14_3") (pintype "bidirectional"))
      (node (ref "IC5") (pin "5") (pinfunction "SYNC_5") (pintype "input"))
    )
    (net (code "19") (name "CS_DAC2") (class "Default")
      (node (ref "IC15") (pin "2") (pinfunction "PC13_2") (pintype "bidirectional"))
      (node (ref "IC4") (pin "5") (pinfunction "SYNC_5") (pintype "input"))
    )
    (net (code "20") (name "CS_POT") (class "Default")
      (node (ref "IC10") (pin "3") (pinfunction "CS_3") (pintype "bidirectional"))
      (node (ref "IC15") (pin "46") (pinfunction "PB9_46") (pintype "bidirectional"))
    )
    (net (code "21") (name "CURRENT_CTRL_SINK") (class "Default")
      (node (ref "IC4") (pin "4") (pinfunction "VOUTA_4") (pintype "output"))
      (node (ref "R34") (pin "2") (pinfunction "2_2") (pintype "passive"))
    )
    (net (code "22") (name "CURRENT_CTRL_SOURCE") (class "Default")
      (node (ref "IC3") (pin "12") (pinfunction "+IN_12") (pintype "input"))
      (node (ref "IC4") (pin "3") (pinfunction "VOUTB_3") (pintype "output"))
    )
    (net (code "23") (name "CURRENT_SENSE") (class "Default")
      (node (ref "C19") (pin "2") (pinfunction "2_2") (pintype "passive"))
      (node (ref "C20") (pin "2") (pinfunction "2_2") (pintype "passive"))
      (node (ref "IC13") (pin "6") (pinfunction "OUT_6") (pintype "output"))
      (node (ref "R11") (pin "1") (pinfunction "1_1") (pintype "passive"))
      (node (ref "R15") (pin "2") (pinfunction "2_2") (pintype "passive"))
      (node (ref "R19") (pin "2") (pinfunction "2_2") (pintype "passive"))
      (node (ref "R35") (pin "2") (pinfunction "2_2") (pintype "passive"))
      (node (ref "R36") (pin "2") (pinfunction "2_2") (pintype "passive"))
    )
    (net (code "24") (name "GND") (class "Default")
      (node (ref "C1") (pin "1") (pinfunction "1_1") (pintype "passive"))
      (node (ref "C10") (pin "1") (pinfunction "1_1") (pintype "passive"))
      (node (ref "C12") (pin "2") (pinfunction "2_2") (pintype "passive"))
      (node (ref "C13") (pin "+") (pinfunction "+_+") (pintype "passive"))
      (node (ref "C14") (pin "2") (pinfunction "2_2") (pintype "passive"))
      (node (ref "C15") (pin "2") (pinfunction "2_2") (pintype "passive"))
      (node (ref "C16") (pin "2") (pinfunction "2_2") (pintype "passive"))
      (node (ref "C2") (pin "2") (pinfunction "2_2") (pintype "passive"))
      (node (ref "C21") (pin "2") (pinfunction "2_2") (pintype "passive"))
      (node (ref "C22") (pin "2") (pinfunction "2_2") (pintype "passive"))
      (node (ref "C23") (pin "2") (pinfunction "2_2") (pintype "passive"))
      (node (ref "C24") (pin "2") (pinfunction "2_2") (pintype "passive"))
      (node (ref "C26") (pin "2") (pinfunction "2_2") (pintype "passive"))
      (node (ref "C27") (pin "1") (pinfunction "1_1") (pintype "passive"))
      (node (ref "C28") (pin "1") (pinfunction "1_1") (pintype "passive"))
      (node (ref "C29") (pin "-") (pinfunction "-_-") (pintype "passive"))
      (node (ref "C3") (pin "2") (pinfunction "2_2") (pintype "passive"))
      (node (ref "C30") (pin "1") (pinfunction "1_1") (pintype "passive"))
      (node (ref "C32") (pin "2") (pinfunction "2_2") (pintype "passive"))
      (node (ref "C34") (pin "1") (pinfunction "1_1") (pintype "passive"))
      (node (ref "C35") (pin "-") (pinfunction "-_-") (pintype "passive"))
      (node (ref "C36") (pin "1") (pinfunction "1_1") (pintype "passive"))
      (node (ref "C38") (pin "2") (pinfunction "2_2") (pintype "passive"))
      (node (ref "C4") (pin "2") (pinfunction "2_2") (pintype "passive"))
      (node (ref "C42") (pin "-") (pinfunction "-_-") (pintype "passive"))
      (node (ref "C44") (pin "2") (pinfunction "2_2") (pintype "passive"))
      (node (ref "C46") (pin "2") (pinfunction "2_2") (pintype "passive"))
      (node (ref "C47") (pin "2") (pinfunction "2_2") (pintype "passive"))
      (node (ref "C48") (pin "2") (pinfunction "2_2") (pintype "passive"))
      (node (ref "C51") (pin "2") (pinfunction "2_2") (pintype "passive"))
      (node (ref "C6") (pin "2") (pinfunction "2_2") (pintype "passive"))
      (node (ref "C7") (pin "2") (pinfunction "2_2") (pintype "passive"))
      (node (ref "C8") (pin "2") (pinfunction "2_2") (pintype "passive"))
      (node (ref "C9") (pin "2") (pinfunction "2_2") (pintype "passive"))
      (node (ref "D1") (pin "1") (pinfunction "A1_1") (pintype "passive"))
      (node (ref "D10") (pin "A") (pinfunction "A_A") (pintype "passive"))
      (node (ref "D2") (pin "1") (pinfunction "A1_1") (pintype "passive"))
      (node (ref "D6") (pin "1") (pinfunction "A1_1") (pintype "passive"))
      (node (ref "D7") (pin "1") (pinfunction "A1_1") (pintype "passive"))
      (node (ref "D8") (pin "C") (pinfunction "C_C") (pintype "passive"))
      (node (ref "GND") (pin "1") (pinfunction "P_1") (pintype "passive"))
      (node (ref "IC10") (pin "6") (pinfunction "WLAT_6") (pintype "bidirectional"))
      (node (ref "IC10") (pin "9") (pinfunction "DGND_9") (pintype "bidirectional"))
      (node (ref "IC11") (pin "2") (pinfunction "VSS_2") (pintype "bidirectional"))
      (node (ref "IC12") (pin "3") (pinfunction "INH_3") (pintype "input"))
      (node (ref "IC12") (pin "7") (pinfunction "GND_7") (pintype "power_in"))
      (node (ref "IC12") (pin "EXP") (pinfunction "EXP_EXP") (pintype "input"))
      (node (ref "IC15") (pin "23") (pinfunction "VSS_23") (pintype "power_in"))
      (node (ref "IC15") (pin "44") (pinfunction "BOOT0_44") (pintype "input"))
      (node (ref "IC15") (pin "47") (pinfunction "VSS_47") (pintype "power_in"))
      (node (ref "IC15") (pin "8") (pinfunction "VSSA_8") (pintype "power_in"))
      (node (ref "IC16") (pin "12") (pinfunction "+IN_12") (pintype "input"))
      (node (ref "IC16") (pin "3") (pinfunction "+IN_3") (pintype "input"))
      (node (ref "IC16") (pin "5") (pinfunction "+IN_5") (pintype "input"))
      (node (ref "IC22") (pin "1") (pinfunction "GND_1") (pintype "power_in"))
      (node (ref "IC3") (pin "3") (pinfunction "+IN_3") (pintype "input"))
      (node (ref "IC3") (pin "5") (pinfunction "+IN_5") (pintype "input"))
      (node (ref "IC4") (pin "8") (pinfunction "GND_8") (pintype "power_in"))
      (node (ref "IC5") (pin "8") (pinfunction "GND_8") (pintype "power_in"))
      (node (ref "IC7") (pin "10") (pinfunction "+IN_10") (pintype "input"))
      (node (ref "IC8") (pin "15") (pinfunction "GND2_15") (pintype "input"))
      (node (ref "IC8") (pin "9") (pinfunction "GND2_9") (pintype "input"))
      (node (ref "IC9") (pin "2") (pinfunction "GND_2") (pintype "power_in"))
      (node (ref "Q1") (pin "C") (pinfunction "C_C") (pintype "passive"))
      (node (ref "Q11") (pin "E") (pinfunction "E_E") (pintype "passive"))
      (node (ref "Q12") (pin "E") (pinfunction "E_E") (pintype "passive"))
      (node (ref "Q13") (pin "E") (pinfunction "E_E") (pintype "passive"))
      (node (ref "Q3") (pin "E") (pinfunction "E_E") (pintype "passive"))
      (node (ref "R10") (pin "2") (pinfunction "2_2") (pintype "passive"))
      (node (ref "R17") (pin "2") (pinfunction "2_2") (pintype "passive"))
      (node (ref "R21") (pin "2") (pinfunction "2_2") (pintype "passive"))
      (node (ref "R32") (pin "2") (pinfunction "2_2") (pintype "passive"))
      (node (ref "R38") (pin "2") (pinfunction "2_2") (pintype "passive"))
      (node (ref "R43") (pin "2") (pinfunction "2_2") (pintype "passive"))
      (node (ref "R44") (pin "1") (pinfunction "1_1") (pintype "passive"))
      (node (ref "R49") (pin "1") (pinfunction "1_1") (pintype "passive"))
      (node (ref "R53") (pin "1") (pinfunction "1_1") (pintype "passive"))
      (node (ref "R54") (pin "1") (pinfunction "1_1") (pintype "passive"))
      (node (ref "R55") (pin "1") (pinfunction "1_1") (pintype "passive"))
      (node (ref "R59") (pin "2") (pinfunction "2_2") (pintype "passive"))
      (node (ref "R6") (pin "2") (pinfunction "2_2") (pintype "passive"))
      (node (ref "R62") (pin "2") (pinfunction "2_2") (pintype "passive"))
      (node (ref "R67") (pin "2") (pinfunction "2_2") (pintype "passive"))
      (node (ref "R7") (pin "2") (pinfunction "2_2") (pintype "passive"))
      (node (ref "R8") (pin "2") (pinfunction "2_2") (pintype "passive"))
      (node (ref "R9") (pin "2") (pinfunction "2_2") (pintype "passive"))
      (node (ref "SDIO") (pin "3") (pinfunction "3_3") (pintype "passive"))
      (node (ref "V1") (pin "1") (pinfunction "-VIN_1") (pintype "passive"))
    )
    (net (code "25") (name "GND1") (class "Default")
      (node (ref "FRONTPANEL") (pin "6") (pinfunction "6_6") (pintype "passive"))
      (node (ref "IC8") (pin "2") (pinfunction "GND1_2") (pintype "input"))
      (node (ref "IC8") (pin "8") (pinfunction "GND1_8") (pintype "input"))
      (node (ref "V1") (pin "3") (pinfunction "-VOUT_3") (pintype "passive"))
    )
    (net (code "26") (name "INT_MISO") (class "Default")
      (node (ref "IC10") (pin "5") (pinfunction "SDO_5") (pintype "bidirectional"))
      (node (ref "IC15") (pin "40") (pinfunction "PB4_40") (pintype "bidirectional"))
    )
    (net (code "27") (name "INT_MOSI") (class "Default")
      (node (ref "IC10") (pin "4") (pinfunction "SDI_4") (pintype "bidirectional"))
      (node (ref "IC15") (pin "41") (pinfunction "PB5_41") (pintype "bidirectional"))
      (node (ref "IC4") (pin "7") (pinfunction "DIN_7") (pintype "input"))
      (node (ref "IC5") (pin "7") (pinfunction "DIN_7") (pintype "input"))
    )
    (net (code "28") (name "INT_SCK") (class "Default")
      (node (ref "IC10") (pin "2") (pinfunction "SCK_2") (pintype "bidirectional"))
      (node (ref "IC15") (pin "39") (pinfunction "PB3_39") (pintype "bidirectional"))
      (node (ref "IC4") (pin "6") (pinfunction "SCLK_6") (pintype "input"))
      (node (ref "IC5") (pin "6") (pinfunction "SCLK_6") (pintype "input"))
    )
    (net (code "29") (name "Net-(C1-Pad2)") (class "Default")
      (node (ref "C1") (pin "2") (pinfunction "2_2") (pintype "passive"))
      (node (ref "C39") (pin "1") (pinfunction "1_1") (pintype "passive"))
      (node (ref "L5") (pin "2") (pinfunction "2_2") (pintype "passive"))
      (node (ref "L8") (pin "1") (pinfunction "1_1") (pintype "passive"))
      (node (ref "R57") (pin "2") (pinfunction "2_2") (pintype "passive"))
    )
    (net (code "30") (name "Net-(C16-Pad1)") (class "Default")
      (node (ref "C16") (pin "1") (pinfunction "1_1") (pintype "passive"))
      (node (ref "R41") (pin "2") (pinfunction "2_2") (pintype "passive"))
      (node (ref "R42") (pin "1") (pinfunction "1_1") (pintype "passive"))
    )
    (net (code "31") (name "Net-(C33-Pad2)") (class "Default")
      (node (ref "C33") (pin "2") (pinfunction "2_2") (pintype "passive"))
      (node (ref "R54") (pin "2") (pinfunction "2_2") (pintype "passive"))
    )
    (net (code "32") (name "Net-(C37-Pad1)") (class "Default")
      (node (ref "C37") (pin "1") (pinfunction "1_1") (pintype "passive"))
      (node (ref "D8") (pin "A") (pinfunction "A_A") (pintype "passive"))
      (node (ref "L5") (pin "1") (pinfunction "1_1") (pintype "passive"))
    )
    (net (code "33") (name "Net-(C38-Pad1)") (class "Default")
      (node (ref "C38") (pin "1") (pinfunction "1_1") (pintype "passive"))
      (node (ref "R55") (pin "2") (pinfunction "2_2") (pintype "passive"))
      (node (ref "R56") (pin "1") (pinfunction "1_1") (pintype "passive"))
    )
    (net (code "34") (name "Net-(D3-A)") (class "Default")
      (node (ref "D3") (pin "2") (pinfunction "A_2") (pintype "passive"))
      (node (ref "D5") (pin "2") (pinfunction "A_2") (pintype "passive"))
      (node (ref "Q5") (pin "B") (pinfunction "B_B") (pintype "passive"))
      (node (ref "Q8") (pin "B") (pinfunction "B_B") (pintype "passive"))
      (node (ref "Q8") (pin "C") (pinfunction "C_C") (pintype "passive"))
    )
    (net (code "35") (name "Net-(D3-C)") (class "Default")
      (node (ref "D3") (pin "1") (pinfunction "C_1") (pintype "passive"))
      (node (ref "Q14") (pin "E") (pinfunction "E_E") (pintype "passive"))
    )
    (net (code "36") (name "Net-(D4-A)") (class "Default")
      (node (ref "D4") (pin "2") (pinfunction "A_2") (pintype "passive"))
      (node (ref "K1") (pin "1") (pinfunction "1_1") (pintype "passive"))
      (node (ref "Q13") (pin "C") (pinfunction "C_C") (pintype "passive"))
    )
    (net (code "37") (name "Net-(D5-C)") (class "Default")
      (node (ref "C18") (pin "2") (pinfunction "2_2") (pintype "passive"))
      (node (ref "D5") (pin "1") (pinfunction "C_1") (pintype "passive"))
      (node (ref "IC3") (pin "14") (pinfunction "OUT_14") (pintype "output"))
    )
    (net (code "38") (name "Net-(IC1-+IN)") (class "Default")
      (node (ref "IC1") (pin "3") (pinfunction "+IN_3") (pintype "input"))
      (node (ref "R18") (pin "1") (pinfunction "1_1") (pintype "passive"))
      (node (ref "R21") (pin "1") (pinfunction "1_1") (pintype "passive"))
    )
    (net (code "39") (name "Net-(IC1--IN)") (class "Default")
      (node (ref "IC1") (pin "2") (pinfunction "-IN_2") (pintype "input"))
      (node (ref "R19") (pin "1") (pinfunction "1_1") (pintype "passive"))
      (node (ref "R20") (pin "2") (pinfunction "2_2") (pintype "passive"))
    )
    (net (code "40") (name "Net-(IC1-OUT)") (class "Default")
      (node (ref "IC1") (pin "6") (pinfunction "OUT_6") (pintype "output"))
      (node (ref "R20") (pin "1") (pinfunction "1_1") (pintype "passive"))
      (node (ref "R25") (pin "2") (pinfunction "2_2") (pintype "passive"))
    )
    (net (code "41") (name "Net-(IC2-+IN)") (class "Default")
      (node (ref "IC2") (pin "3") (pinfunction "+IN_3") (pintype "input"))
      (node (ref "R14") (pin "1") (pinfunction "1_1") (pintype "passive"))
      (node (ref "R17") (pin "1") (pinfunction "1_1") (pintype "passive"))
    )
    (net (code "42") (name "Net-(IC2--IN)") (class "Default")
      (node (ref "IC2") (pin "2") (pinfunction "-IN_2") (pintype "input"))
      (node (ref "R15") (pin "1") (pinfunction "1_1") (pintype "passive"))
      (node (ref "R16") (pin "2") (pinfunction "2_2") (pintype "passive"))
    )
    (net (code "43") (name "Net-(IC2-OUT)") (class "Default")
      (node (ref "IC2") (pin "6") (pinfunction "OUT_6") (pintype "output"))
      (node (ref "R16") (pin "1") (pinfunction "1_1") (pintype "passive"))
      (node (ref "R24") (pin "2") (pinfunction "2_2") (pintype "passive"))
    )
    (net (code "44") (name "Net-(IC3B--IN)") (class "Default")
      (node (ref "IC3") (pin "6") (pinfunction "-IN_6") (pintype "input"))
      (node (ref "IC3") (pin "7") (pinfunction "OUT_7") (pintype "output"))
    )
    (net (code "45") (name "Net-(IC3D--IN)") (class "Default")
      (node (ref "C18") (pin "1") (pinfunction "1_1") (pintype "passive"))
      (node (ref "C19") (pin "1") (pinfunction "1_1") (pintype "passive"))
      (node (ref "IC3") (pin "13") (pinfunction "-IN_13") (pintype "input"))
      (node (ref "R35") (pin "1") (pinfunction "1_1") (pintype "passive"))
    )
    (net (code "46") (name "Net-(IC6-R)") (class "Default")
      (node (ref "IC6") (pin "2") (pinfunction "R_2") (pintype "passive"))
      (node (ref "R45") (pin "1") (pinfunction "1_1") (pintype "passive"))
    )
    (net (code "47") (name "Net-(IC7A-+IN)") (class "Default")
      (node (ref "IC7") (pin "3") (pinfunction "+IN_3") (pintype "input"))
      (node (ref "R13") (pin "1") (pinfunction "1_1") (pintype "passive"))
      (node (ref "R22") (pin "1") (pinfunction "1_1") (pintype "passive"))
      (node (ref "R23") (pin "1") (pinfunction "1_1") (pintype "passive"))
    )
    (net (code "48") (name "Net-(IC7A--IN)") (class "Default")
      (node (ref "C5") (pin "1") (pinfunction "1_1") (pintype "passive"))
      (node (ref "IC7") (pin "2") (pinfunction "-IN_2") (pintype "input"))
      (node (ref "R12") (pin "1") (pinfunction "1_1") (pintype "passive"))
      (node (ref "R29") (pin "1") (pinfunction "1_1") (pintype "passive"))
      (node (ref "R44") (pin "2") (pinfunction "2_2") (pintype "passive"))
    )
    (net (code "49") (name "Net-(IC7A-OUT)") (class "Default")
      (node (ref "C5") (pin "2") (pinfunction "2_2") (pintype "passive"))
      (node (ref "IC7") (pin "1") (pinfunction "OUT_1") (pintype "output"))
      (node (ref "Q14") (pin "B") (pinfunction "B_B") (pintype "passive"))
    )
    (net (code "50") (name "Net-(IC7B--IN)") (class "Default")
      (node (ref "IC7") (pin "6") (pinfunction "-IN_6") (pintype "input"))
      (node (ref "R30") (pin "2") (pinfunction "2_2") (pintype "passive"))
      (node (ref "R32") (pin "1") (pinfunction "1_1") (pintype "passive"))
    )
    (net (code "51") (name "Net-(IC7B-OUT)") (class "Default")
      (node (ref "IC7") (pin "7") (pinfunction "OUT_7") (pintype "output"))
      (node (ref "R23") (pin "2") (pinfunction "2_2") (pintype "passive"))
      (node (ref "R30") (pin "1") (pinfunction "1_1") (pintype "passive"))
    )
    (net (code "52") (name "Net-(IC7C--IN)") (class "Default")
      (node (ref "IC7") (pin "9") (pinfunction "-IN_9") (pintype "input"))
      (node (ref "R33") (pin "2") (pinfunction "2_2") (pintype "passive"))
      (node (ref "R34") (pin "1") (pinfunction "1_1") (pintype "passive"))
    )
    (net (code "53") (name "Net-(IC7C-OUT)") (class "Default")
      (node (ref "IC7") (pin "12") (pinfunction "+IN_12") (pintype "input"))
      (node (ref "IC7") (pin "8") (pinfunction "OUT_8") (pintype "output"))
      (node (ref "R33") (pin "1") (pinfunction "1_1") (pintype "passive"))
    )
    (net (code "54") (name "Net-(IC7D--IN)") (class "Default")
      (node (ref "C17") (pin "1") (pinfunction "1_1") (pintype "passive"))
      (node (ref "C20") (pin "1") (pinfunction "1_1") (pintype "passive"))
      (node (ref "IC7") (pin "13") (pinfunction "-IN_13") (pintype "input"))
      (node (ref "R36") (pin "1") (pinfunction "1_1") (pintype "passive"))
    )
    (net (code "55") (name "Net-(IC7D-OUT)") (class "Default")
      (node (ref "C17") (pin "2") (pinfunction "2_2") (pintype "passive"))
      (node (ref "IC7") (pin "14") (pinfunction "OUT_14") (pintype "output"))
      (node (ref "Q14") (pin "C") (pinfunction "C_C") (pintype "passive"))
    )
    (net (code "56") (name "Net-(IC8-VDD1)") (class "Default")
      (node (ref "FRONTPANEL") (pin "2") (pinfunction "2_2") (pintype "passive"))
      (node (ref "IC8") (pin "1") (pinfunction "VDD1_1") (pintype "input"))
      (node (ref "IC8") (pin "7") (pinfunction "VE1_7") (pintype "input"))
    )
    (net (code "57") (name "Net-(IC8-VIA)") (class "Default")
      (node (ref "FRONTPANEL") (pin "3") (pinfunction "3_3") (pintype "passive"))
      (node (ref "IC8") (pin "3") (pinfunction "VIA_3") (pintype "input"))
    )
    (net (code "58") (name "Net-(IC8-VIB)") (class "Default")
      (node (ref "FRONTPANEL") (pin "4") (pinfunction "4_4") (pintype "passive"))
      (node (ref "IC8") (pin "4") (pinfunction "VIB_4") (pintype "input"))
    )
    (net (code "59") (name "Net-(IC8-VOC)") (class "Default")
      (node (ref "FRONTPANEL") (pin "5") (pinfunction "5_5") (pintype "passive"))
      (node (ref "IC8") (pin "5") (pinfunction "VOC_5") (pintype "tri_state"))
    )
    (net (code "60") (name "Net-(IC9-NFB)") (class "Default")
      (node (ref "C39") (pin "2") (pinfunction "2_2") (pintype "passive"))
      (node (ref "IC9") (pin "3") (pinfunction "NFB_3") (pintype "input"))
      (node (ref "R56") (pin "2") (pinfunction "2_2") (pintype "passive"))
      (node (ref "R57") (pin "1") (pinfunction "1_1") (pintype "passive"))
    )
    (net (code "61") (name "Net-(IC9-SW)") (class "Default")
      (node (ref "C37") (pin "2") (pinfunction "2_2") (pintype "passive"))
      (node (ref "IC9") (pin "1") (pinfunction "SW_1") (pintype "output"))
      (node (ref "L4") (pin "2") (pinfunction "2_2") (pintype "passive"))
    )
    (net (code "62") (name "Net-(IC10-P0W)") (class "Default")
      (node (ref "IC10") (pin "12") (pinfunction "P0W_12") (pintype "bidirectional"))
      (node (ref "IC3") (pin "2") (pinfunction "-IN_2") (pintype "input"))
    )
    (net (code "63") (name "Net-(IC11-VOUT)") (class "Default")
      (node (ref "IC11") (pin "1") (pinfunction "VOUT_1") (pintype "bidirectional"))
      (node (ref "R39") (pin "1") (pinfunction "1_1") (pintype "passive"))
    )
    (net (code "64") (name "Net-(IC12B-COMP)") (class "Default")
      (node (ref "C32") (pin "1") (pinfunction "1_1") (pintype "passive"))
      (node (ref "C33") (pin "1") (pinfunction "1_1") (pintype "passive"))
      (node (ref "IC12") (pin "4") (pinfunction "COMP_4") (pintype "passive"))
    )
    (net (code "65") (name "Net-(IC12B-FB)") (class "Default")
      (node (ref "IC12") (pin "5") (pinfunction "FB_5") (pintype "input"))
      (node (ref "R52") (pin "1") (pinfunction "1_1") (pintype "passive"))
      (node (ref "R53") (pin "2") (pinfunction "2_2") (pintype "passive"))
    )
    (net (code "66") (name "Net-(IC12B-OUT)") (class "Default")
      (node (ref "D10") (pin "C") (pinfunction "C_C") (pintype "passive"))
      (node (ref "IC12") (pin "1") (pinfunction "OUT_1") (pintype "output"))
      (node (ref "L3") (pin "1") (pinfunction "1_1") (pintype "passive"))
    )
    (net (code "67") (name "Net-(IC13A-IN+)") (class "Default")
      (node (ref "BAT_OUT") (pin "5") (pinfunction "5_5") (pintype "passive"))
      (node (ref "BAT_OUT") (pin "6") (pinfunction "6_6") (pintype "passive"))
      (node (ref "BAT_OUT") (pin "7") (pinfunction "7_7") (pintype "passive"))
      (node (ref "BAT_OUT") (pin "8") (pinfunction "8_8") (pintype "passive"))
      (node (ref "IC13") (pin "3") (pinfunction "IN+_3") (pintype "input"))
      (node (ref "IC3") (pin "10") (pinfunction "+IN_10") (pintype "input"))
      (node (ref "R7") (pin "1") (pinfunction "1_1") (pintype "passive"))
      (node (ref "R8") (pin "1") (pinfunction "1_1") (pintype "passive"))
      (node (ref "R9") (pin "1") (pinfunction "1_1") (pintype "passive"))
    )
    (net (code "68") (name "Net-(IC13A-IN-)") (class "Default")
      (node (ref "IC13") (pin "2") (pinfunction "IN-_2") (pintype "input"))
      (node (ref "R10") (pin "1") (pinfunction "1_1") (pintype "passive"))
      (node (ref "R11") (pin "2") (pinfunction "2_2") (pintype "passive"))
    )
    (net (code "69") (name "Net-(IC15A-NRST)") (class "Default")
      (node (ref "IC15") (pin "7") (pinfunction "NRST_7") (pintype "bidirectional"))
      (node (ref "SDIO") (pin "5") (pinfunction "5_5") (pintype "passive"))
    )
    (net (code "70") (name "Net-(IC15A-PA13)") (class "Default")
      (node (ref "IC15") (pin "34") (pinfunction "PA13_34") (pintype "bidirectional"))
      (node (ref "SDIO") (pin "4") (pinfunction "4_4") (pintype "passive"))
    )
    (net (code "71") (name "Net-(IC15A-PA14)") (class "Default")
      (node (ref "IC15") (pin "37") (pinfunction "PA14_37") (pintype "bidirectional"))
      (node (ref "SDIO") (pin "2") (pinfunction "2_2") (pintype "passive"))
    )
    (net (code "72") (name "Net-(IC15A-PB13)") (class "Default")
      (node (ref "IC15") (pin "26") (pinfunction "PB13_26") (pintype "bidirectional"))
      (node (ref "IC8") (pin "13") (pinfunction "VOB_13") (pintype "tri_state"))
    )
    (net (code "73") (name "Net-(IC15A-PB14)") (class "Default")
      (node (ref "IC15") (pin "27") (pinfunction "PB14_27") (pintype "bidirectional"))
      (node (ref "IC8") (pin "12") (pinfunction "VIC_12") (pintype "input"))
    )
    (net (code "74") (name "Net-(IC15A-PB15)") (class "Default")
      (node (ref "IC15") (pin "28") (pinfunction "PB15_28") (pintype "bidirectional"))
      (node (ref "IC8") (pin "14") (pinfunction "VOA_14") (pintype "tri_state"))
    )
    (net (code "75") (name "Net-(IC16A--IN)") (class "Default")
      (node (ref "IC16") (pin "2") (pinfunction "-IN_2") (pintype "input"))
      (node (ref "R39") (pin "2") (pinfunction "2_2") (pintype "passive"))
      (node (ref "R40") (pin "1") (pinfunction "1_1") (pintype "passive"))
    )
    (net (code "76") (name "Net-(IC16A-OUT)") (class "Default")
      (node (ref "IC16") (pin "1") (pinfunction "OUT_1") (pintype "output"))
      (node (ref "R40") (pin "2") (pinfunction "2_2") (pintype "passive"))
      (node (ref "R41") (pin "1") (pinfunction "1_1") (pintype "passive"))
    )
    (net (code "77") (name "Net-(IC16B--IN)") (class "Default")
      (node (ref "IC16") (pin "6") (pinfunction "-IN_6") (pintype "input"))
      (node (ref "R51") (pin "1") (pinfunction "1_1") (pintype "passive"))
      (node (ref "R63") (pin "2") (pinfunction "2_2") (pintype "passive"))
    )
    (net (code "78") (name "Net-(IC16B-OUT)") (class "Default")
      (node (ref "IC16") (pin "7") (pinfunction "OUT_7") (pintype "output"))
      (node (ref "R63") (pin "1") (pinfunction "1_1") (pintype "passive"))
      (node (ref "R64") (pin "1") (pinfunction "1_1") (pintype "passive"))
    )
    (net (code "79") (name "Net-(IC16C-+IN)") (class "Default")
      (node (ref "IC16") (pin "10") (pinfunction "+IN_10") (pintype "input"))
      (node (ref "R47") (pin "2") (pinfunction "2_2") (pintype "passive"))
      (node (ref "R49") (pin "2") (pinfunction "2_2") (pintype "passive"))
    )
    (net (code "80") (name "Net-(IC16C--IN)") (class "Default")
      (node (ref "IC16") (pin "9") (pinfunction "-IN_9") (pintype "input"))
      (node (ref "R46") (pin "2") (pinfunction "2_2") (pintype "passive"))
      (node (ref "R48") (pin "1") (pinfunction "1_1") (pintype "passive"))
    )
    (net (code "81") (name "Net-(IC16C-OUT)") (class "Default")
      (node (ref "IC16") (pin "8") (pinfunction "OUT_8") (pintype "output"))
      (node (ref "R48") (pin "2") (pinfunction "2_2") (pintype "passive"))
      (node (ref "R50") (pin "1") (pinfunction "1_1") (pintype "passive"))
    )
    (net (code "82") (name "Net-(IC16D--IN)") (class "Default")
      (node (ref "IC16") (pin "13") (pinfunction "-IN_13") (pintype "input"))
      (node (ref "IC16") (pin "14") (pinfunction "OUT_14") (pintype "output"))
    )
    (net (code "83") (name "Net-(Q1-PadB)") (class "Default")
      (node (ref "Q1") (pin "B") (pinfunction "B_B") (pintype "passive"))
      (node (ref "Q3") (pin "C") (pinfunction "C_C") (pintype "passive"))
      (node (ref "R5") (pin "1") (pinfunction "1_1") (pintype "passive"))
    )
    (net (code "84") (name "Net-(Q2-PadB)") (class "Default")
      (node (ref "Q2") (pin "B") (pinfunction "B_B") (pintype "passive"))
      (node (ref "Q4") (pin "C") (pinfunction "C_C") (pintype "passive"))
      (node (ref "R1") (pin "2") (pinfunction "2_2") (pintype "passive"))
    )
    (net (code "85") (name "Net-(Q3-PadB)") (class "Default")
      (node (ref "Q3") (pin "B") (pinfunction "B_B") (pintype "passive"))
      (node (ref "Q5") (pin "C") (pinfunction "C_C") (pintype "passive"))
      (node (ref "R6") (pin "1") (pinfunction "1_1") (pintype "passive"))
    )
    (net (code "86") (name "Net-(Q4-PadB)") (class "Default")
      (node (ref "Q4") (pin "B") (pinfunction "B_B") (pintype "passive"))
      (node (ref "Q6") (pin "C") (pinfunction "C_C") (pintype "passive"))
      (node (ref "R2") (pin "1") (pinfunction "1_1") (pintype "passive"))
    )
    (net (code "87") (name "Net-(Q7-PadE)") (class "Default")
      (node (ref "Q7") (pin "E") (pinfunction "E_E") (pintype "passive"))
      (node (ref "Q8") (pin "E") (pinfunction "E_E") (pintype "passive"))
    )
    (net (code "88") (name "Net-(Q9-PadE)") (class "Default")
      (node (ref "Q9") (pin "E") (pinfunction "E_E") (pintype "passive"))
      (node (ref "R27") (pin "1") (pinfunction "1_1") (pintype "passive"))
    )
    (net (code "89") (name "Net-(Q10-PadB)") (class "Default")
      (node (ref "Q10") (pin "B") (pinfunction "B_B") (pintype "passive"))
      (node (ref "Q10") (pin "C") (pinfunction "C_C") (pintype "passive"))
      (node (ref "Q11") (pin "C") (pinfunction "C_C") (pintype "passive"))
      (node (ref "Q9") (pin "B") (pinfunction "B_B") (pintype "passive"))
    )
    (net (code "90") (name "Net-(Q10-PadE)") (class "Default")
      (node (ref "Q10") (pin "E") (pinfunction "E_E") (pintype "passive"))
      (node (ref "R26") (pin "1") (pinfunction "1_1") (pintype "passive"))
    )
    (net (code "91") (name "Net-(Q11-PadB)") (class "Default")
      (node (ref "Q11") (pin "B") (pinfunction "B_B") (pintype "passive"))
      (node (ref "Q12") (pin "B") (pinfunction "B_B") (pintype "passive"))
      (node (ref "Q12") (pin "C") (pinfunction "C_C") (pintype "passive"))
      (node (ref "R28") (pin "1") (pinfunction "1_1") (pintype "passive"))
    )
    (net (code "92") (name "Net-(Q13-PadB)") (class "Default")
      (node (ref "Q13") (pin "B") (pinfunction "B_B") (pintype "passive"))
      (node (ref "R31") (pin "2") (pinfunction "2_2") (pintype "passive"))
    )
    (net (code "93") (name "Net-(R42-Pad2)") (class "Default")
      (node (ref "R42") (pin "2") (pinfunction "2_2") (pintype "passive"))
      (node (ref "VIN_CTRL") (pin "1") (pinfunction "1_1") (pintype "passive"))
    )
    (net (code "94") (name "Net-(V1-+VIN)") (class "Default")
      (node (ref "C11") (pin "1") (pinfunction "1_1") (pintype "passive"))
      (node (ref "L1") (pin "2") (pinfunction "2_2") (pintype "passive"))
      (node (ref "V1") (pin "2") (pinfunction "+VIN_2") (pintype "passive"))
    )
    (net (code "95") (name "OUTPUT_ENABLE") (class "Default")
      (node (ref "IC15") (pin "38") (pinfunction "PA15_38") (pintype "bidirectional"))
      (node (ref "R31") (pin "1") (pinfunction "1_1") (pintype "passive"))
    )
    (net (code "96") (name "PUSHPULL_OUT") (class "Default")
      (node (ref "C28") (pin "2") (pinfunction "2_2") (pintype "passive"))
      (node (ref "K1") (pin "P") (pinfunction "P_P") (pintype "passive"))
      (node (ref "R12") (pin "2") (pinfunction "2_2") (pintype "passive"))
      (node (ref "R29") (pin "2") (pinfunction "2_2") (pintype "passive"))
      (node (ref "R3") (pin "1") (pinfunction "1_1") (pintype "passive"))
      (node (ref "R4") (pin "2") (pinfunction "2_2") (pintype "passive"))
      (node (ref "R60") (pin "1") (pinfunction "1_1") (pintype "passive"))
    )
    (net (code "97") (name "RI_COMP") (class "Default")
      (node (ref "IC10") (pin "13") (pinfunction "P0A_13") (pintype "bidirectional"))
      (node (ref "IC3") (pin "1") (pinfunction "OUT_1") (pintype "output"))
      (node (ref "R13") (pin "2") (pinfunction "2_2") (pintype "passive"))
    )
    (net (code "98") (name "SCL") (class "Default")
      (node (ref "IC11") (pin "5") (pinfunction "SCL_5") (pintype "bidirectional"))
      (node (ref "IC15") (pin "21") (pinfunction "PB10_21") (pintype "bidirectional"))
      (node (ref "R65") (pin "1") (pinfunction "1_1") (pintype "passive"))
    )
    (net (code "99") (name "SDA") (class "Default")
      (node (ref "IC11") (pin "4") (pinfunction "SDA_4") (pintype "bidirectional"))
      (node (ref "IC15") (pin "22") (pinfunction "PB11_22") (pintype "bidirectional"))
      (node (ref "R66") (pin "1") (pinfunction "1_1") (pintype "passive"))
    )
    (net (code "100") (name "SENSE_COMP") (class "Default")
      (node (ref "IC10") (pin "11") (pinfunction "P0B_11") (pintype "bidirectional"))
      (node (ref "IC3") (pin "8") (pinfunction "OUT_8") (pintype "output"))
      (node (ref "IC3") (pin "9") (pinfunction "-IN_9") (pintype "input"))
      (node (ref "R22") (pin "2") (pinfunction "2_2") (pintype "passive"))
    )
    (net (code "101") (name "VIN") (class "Default")
      (node (ref "C34") (pin "2") (pinfunction "2_2") (pintype "passive"))
      (node (ref "IC12") (pin "8") (pinfunction "VCC_8") (pintype "input"))
      (node (ref "L7") (pin "1") (pinfunction "1_1") (pintype "passive"))
      (node (ref "Q2") (pin "C") (pinfunction "C_C") (pintype "passive"))
      (node (ref "Q4") (pin "E") (pinfunction "E_E") (pintype "passive"))
      (node (ref "R2") (pin "2") (pinfunction "2_2") (pintype "passive"))
      (node (ref "VIN") (pin "1") (pinfunction "P_1") (pintype "passive"))
    )
    (net (code "102") (name "VOLTAGE_CTRL") (class "Default")
      (node (ref "IC5") (pin "3") (pinfunction "VOUTB_3") (pintype "output"))
      (node (ref "IC7") (pin "5") (pinfunction "+IN_5") (pintype "input"))
    )
    (net (code "103") (name "VOUT_HIGHSIDE") (class "Default")
      (node (ref "Q2") (pin "E") (pinfunction "E_E") (pintype "passive"))
      (node (ref "Q6") (pin "E") (pinfunction "E_E") (pintype "passive"))
      (node (ref "R1") (pin "1") (pinfunction "1_1") (pintype "passive"))
      (node (ref "R3") (pin "2") (pinfunction "2_2") (pintype "passive"))
      (node (ref "R47") (pin "1") (pinfunction "1_1") (pintype "passive"))
    )
    (net (code "104") (name "VOUT_LOWSIDE") (class "Default")
      (node (ref "Q1") (pin "E") (pinfunction "E_E") (pintype "passive"))
      (node (ref "Q5") (pin "E") (pinfunction "E_E") (pintype "passive"))
      (node (ref "R4") (pin "1") (pinfunction "1_1") (pintype "passive"))
      (node (ref "R46") (pin "1") (pinfunction "1_1") (pintype "passive"))
      (node (ref "R5") (pin "2") (pinfunction "2_2") (pintype "passive"))
    )
    (net (code "105") (name "VREF") (class "Default")
      (node (ref "C12") (pin "1") (pinfunction "1_1") (pintype "passive"))
      (node (ref "C6") (pin "1") (pinfunction "1_1") (pintype "passive"))
      (node (ref "IC11") (pin "6") (pinfunction "VREF_6") (pintype "bidirectional"))
      (node (ref "IC15") (pin "9") (pinfunction "VDDA_9") (pintype "power_in"))
      (node (ref "IC4") (pin "2") (pinfunction "VREF_2") (pintype "input"))
      (node (ref "IC5") (pin "2") (pinfunction "VREF_2") (pintype "input"))
      (node (ref "L2") (pin "2") (pinfunction "2_2") (pintype "passive"))
      (node (ref "R14") (pin "2") (pinfunction "2_2") (pintype "passive"))
      (node (ref "R18") (pin "2") (pinfunction "2_2") (pintype "passive"))
    )
    (net (code "106") (name "unconnected-(IC1-ON1-Pad1)") (class "Default")
      (node (ref "IC1") (pin "1") (pinfunction "ON1_1") (pintype "passive"))
    )
    (net (code "107") (name "unconnected-(IC1-ON2-Pad8)") (class "Default")
      (node (ref "IC1") (pin "8") (pinfunction "ON2_8") (pintype "passive"))
    )
    (net (code "108") (name "unconnected-(IC1-OPT-Pad5)") (class "Default")
      (node (ref "IC1") (pin "5") (pinfunction "OPT_5") (pintype "passive"))
    )
    (net (code "109") (name "unconnected-(IC2-ON1-Pad1)") (class "Default")
      (node (ref "IC2") (pin "1") (pinfunction "ON1_1") (pintype "passive"))
    )
    (net (code "110") (name "unconnected-(IC2-ON2-Pad8)") (class "Default")
      (node (ref "IC2") (pin "8") (pinfunction "ON2_8") (pintype "passive"))
    )
    (net (code "111") (name "unconnected-(IC2-OPT-Pad5)") (class "Default")
      (node (ref "IC2") (pin "5") (pinfunction "OPT_5") (pintype "passive"))
    )
    (net (code "112") (name "unconnected-(IC8-NC-Pad6)") (class "Default")
      (node (ref "IC8") (pin "6") (pinfunction "NC_6") (pintype "no_connect"))
    )
    (net (code "113") (name "unconnected-(IC8-NC-Pad11)") (class "Default")
      (node (ref "IC8") (pin "11") (pinfunction "NC_11") (pintype "no_connect"))
    )
    (net (code "114") (name "unconnected-(IC12B-SYNC-Pad2)") (class "Default")
      (node (ref "IC12") (pin "2") (pinfunction "SYNC_2") (pintype "input"))
    )
    (net (code "115") (name "unconnected-(IC12B-VREF-Pad6)") (class "Default")
      (node (ref "IC12") (pin "6") (pinfunction "VREF_6") (pintype "input"))
    )
    (net (code "116") (name "unconnected-(IC15A-OSC_IN-Pad5)") (class "Default")
      (node (ref "IC15") (pin "5") (pinfunction "OSC_IN_5") (pintype "bidirectional"))
    )
    (net (code "117") (name "unconnected-(IC15A-OSC_OUT-Pad6)") (class "Default")
      (node (ref "IC15") (pin "6") (pinfunction "OSC_OUT_6") (pintype "bidirectional"))
    )
    (net (code "118") (name "unconnected-(IC15A-PA8-Pad29)") (class "Default")
      (node (ref "IC15") (pin "29") (pinfunction "PA8_29") (pintype "bidirectional"))
    )
    (net (code "119") (name "unconnected-(IC15A-PA9-Pad30)") (class "Default")
      (node (ref "IC15") (pin "30") (pinfunction "PA9_30") (pintype "bidirectional"))
    )
    (net (code "120") (name "unconnected-(IC15A-PA10-Pad31)") (class "Default")
      (node (ref "IC15") (pin "31") (pinfunction "PA10_31") (pintype "bidirectional"))
    )
    (net (code "121") (name "unconnected-(IC15A-PA11-Pad32)") (class "Default")
      (node (ref "IC15") (pin "32") (pinfunction "PA11_32") (pintype "bidirectional"))
    )
    (net (code "122") (name "unconnected-(IC15A-PA12-Pad33)") (class "Default")
      (node (ref "IC15") (pin "33") (pinfunction "PA12_33") (pintype "bidirectional"))
    )
    (net (code "123") (name "unconnected-(IC15A-PB1-Pad19)") (class "Default")
      (node (ref "IC15") (pin "19") (pinfunction "PB1_19") (pintype "bidirectional"))
    )
    (net (code "124") (name "unconnected-(IC15A-PB2-Pad20)") (class "Default")
      (node (ref "IC15") (pin "20") (pinfunction "PB2_20") (pintype "bidirectional"))
    )
    (net (code "125") (name "unconnected-(IC15A-PB6-Pad42)") (class "Default")
      (node (ref "IC15") (pin "42") (pinfunction "PB6_42") (pintype "bidirectional"))
    )
    (net (code "126") (name "unconnected-(IC15A-PB7-Pad43)") (class "Default")
      (node (ref "IC15") (pin "43") (pinfunction "PB7_43") (pintype "bidirectional"))
    )
    (net (code "127") (name "unconnected-(IC15A-PB8-Pad45)") (class "Default")
      (node (ref "IC15") (pin "45") (pinfunction "PB8_45") (pintype "bidirectional"))
    )
    (net (code "128") (name "unconnected-(IC15A-PB12-Pad25)") (class "Default")
      (node (ref "IC15") (pin "25") (pinfunction "PB12_25") (pintype "bidirectional"))
    )
    (net (code "129") (name "unconnected-(IC15A-PC15-Pad4)") (class "Default")
      (node (ref "IC15") (pin "4") (pinfunction "PC15_4") (pintype "bidirectional"))
    )
    (net (code "130") (name "unconnected-(IC15A-PF6-Pad35)") (class "Default")
      (node (ref "IC15") (pin "35") (pinfunction "PF6_35") (pintype "bidirectional"))
    )
    (net (code "131") (name "unconnected-(IC15A-PF7-Pad36)") (class "Default")
      (node (ref "IC15") (pin "36") (pinfunction "PF7_36") (pintype "bidirectional"))
    )
    (net (code "132") (name "unconnected-(K1-PadO)") (class "Default")
      (node (ref "K1") (pin "O") (pinfunction "O_O") (pintype "passive"))
    )
  )
)
